# 6_Auxilaries.net
KiCad netlist of a schematic drawn in Altium Designer
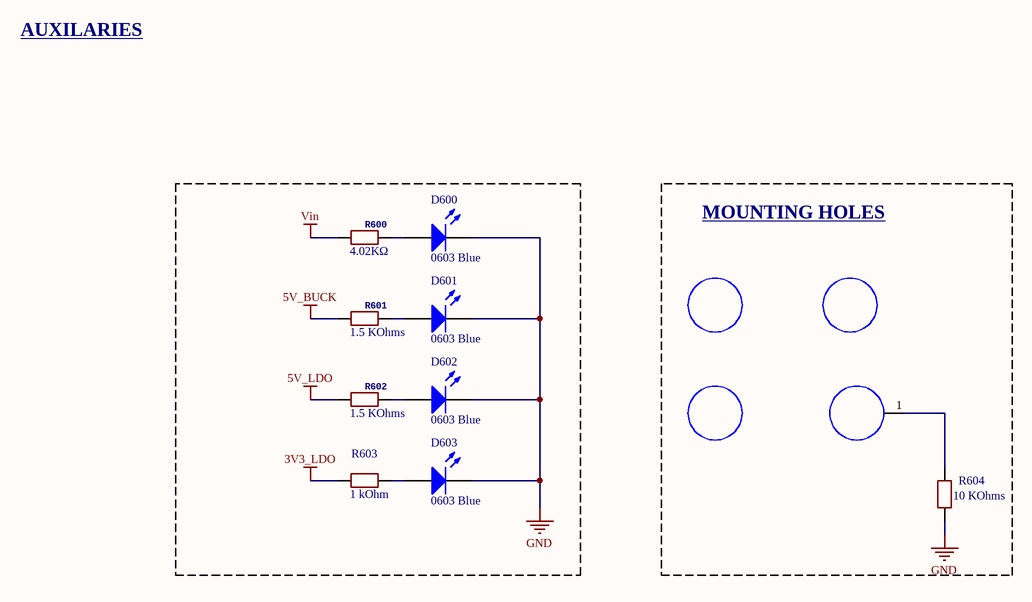
[diagram p0: 6_Auxilaries.SchDoc]

(export (version "E")
  (design (tool "Eeschema 10.0.6"))
  (components
    (comp (ref "D600")
      (value "0603 Blue")
      (footprint "0603_LED_S1")
      (description "LED")
      (libsource (lib "Miscellaneous") (part "0603 LED Blue"))
    )
    (comp (ref "D601")
      (value "0603 Blue")
      (footprint "0603_LED_S1")
      (description "LED")
      (libsource (lib "Miscellaneous") (part "0603 LED Blue"))
    )
    (comp (ref "D602")
      (value "0603 Blue")
      (footprint "0603_LED_S1")
      (description "LED")
      (libsource (lib "Miscellaneous") (part "0603 LED Blue"))
    )
    (comp (ref "D603")
      (value "0603 Blue")
      (footprint "0603_LED_S1")
      (description "LED")
      (libsource (lib "Miscellaneous") (part "0603 LED Blue"))
    )
    (comp (ref "H600")
      (value "M3 not plated")
      (footprint "M3 not plated")
      (description "M3 hole not plated")
      (libsource (lib "Miscellaneous") (part "M3 not plated"))
    )
    (comp (ref "H601")
      (value "M3 not plated")
      (footprint "M3 not plated")
      (description "M3 hole not plated")
      (libsource (lib "Miscellaneous") (part "M3 not plated"))
    )
    (comp (ref "H602")
      (value "M3 plated")
      (footprint "M3 plated")
      (description "M3 hole plated")
      (libsource (lib "Miscellaneous") (part "M3 plated"))
    )
    (comp (ref "H603")
      (value "M3 not plated")
      (footprint "M3 not plated")
      (description "M3 hole not plated")
      (libsource (lib "Miscellaneous") (part "M3 not plated"))
    )
    (comp (ref "R600")
      (value "4.02KΩ")
      (footprint "RES_0603")
      (description "Res 4.02KOhm 1/10W 0603")
      (fields (field (name "PARTNUMBER") "ERJ3GEYJ200V") (field (name "Comment") "ERA3AEB4021V"))
      (libsource (lib "Passives") (part "ERA3AEB4021V"))
    )
    (comp (ref "R601")
      (value "1.5 KOhms")
      (footprint "RES_0603")
      (description "Res 1.5KOhms 1/10W 0603")
      (fields (field (name "PARTNUMBER") "ERJ3EKF1501V"))
      (libsource (lib "Passives") (part "ERJ3EKF1501V"))
    )
    (comp (ref "R602")
      (value "1.5 KOhms")
      (footprint "RES_0603")
      (description "Res 1.5KOhms 1/10W 0603")
      (fields (field (name "PARTNUMBER") "ERJ3EKF1501V"))
      (libsource (lib "Passives") (part "ERJ3EKF1501V"))
    )
    (comp (ref "R603")
      (value "1 kOhm")
      (footprint "RES_0603")
      (description "Res 1kOhm 1/10W 0603")
      (fields (field (name "PARTNUMBER") "ERJ3GEYJ102V"))
      (libsource (lib "Passives") (part "ERJ3GEYJ102V"))
    )
    (comp (ref "R604")
      (value "10 KOhms")
      (footprint "RES_0603")
      (description "Res 10KOhms 1/10W 0603")
      (fields (field (name "PARTNUMBER") "ERJ3GEYJ103V"))
      (libsource (lib "Passives") (part "ERJ3GEYJ103V"))
    )
  )
  (nets
    (net (code "1") (name "3V3_LDO") (class "Default")
      (node (ref "R603") (pin "1") (pinfunction "1_1") (pintype "passive"))
    )
    (net (code "2") (name "5V_BUCK") (class "Default")
      (node (ref "R601") (pin "1") (pinfunction "1_1") (pintype "passive"))
    )
    (net (code "3") (name "5V_LDO") (class "Default")
      (node (ref "R602") (pin "1") (pinfunction "1_1") (pintype "passive"))
    )
    (net (code "4") (name "GND") (class "Default")
      (node (ref "D600") (pin "K") (pinfunction "K_K") (pintype "passive"))
      (node (ref "D601") (pin "K") (pinfunction "K_K") (pintype "passive"))
      (node (ref "D602") (pin "K") (pinfunction "K_K") (pintype "passive"))
      (node (ref "D603") (pin "K") (pinfunction "K_K") (pintype "passive"))
      (node (ref "R604") (pin "2") (pinfunction "2_2") (pintype "passive"))
    )
    (net (code "5") (name "Net-(D600-PadA)") (class "Default")
      (node (ref "D600") (pin "A") (pinfunction "A_A") (pintype "passive"))
      (node (ref "R600") (pin "2") (pinfunction "2_2") (pintype "passive"))
    )
    (net (code "6") (name "Net-(D601-PadA)") (class "Default")
      (node (ref "D601") (pin "A") (pinfunction "A_A") (pintype "passive"))
      (node (ref "R601") (pin "2") (pinfunction "2_2") (pintype "passive"))
    )
    (net (code "7") (name "Net-(D602-PadA)") (class "Default")
      (node (ref "D602") (pin "A") (pinfunction "A_A") (pintype "passive"))
      (node (ref "R602") (pin "2") (pinfunction "2_2") (pintype "passive"))
    )
    (net (code "8") (name "Net-(D603-PadA)") (class "Default")
      (node (ref "D603") (pin "A") (pinfunction "A_A") (pintype "passive"))
      (node (ref "R603") (pin "2") (pinfunction "2_2") (pintype "passive"))
    )
    (net (code "9") (name "Net-(H602-Pad1)") (class "Default")
      (node (ref "H602") (pin "1") (pintype "passive"))
      (node (ref "R604") (pin "1") (pinfunction "1_1") (pintype "passive"))
    )
    (net (code "10") (name "Vin") (class "Default")
      (node (ref "R600") (pin "1") (pinfunction "1_1") (pintype "passive"))
    )
  )
)
